# 10.net
KiCad netlist of a schematic drawn in Altium Designer
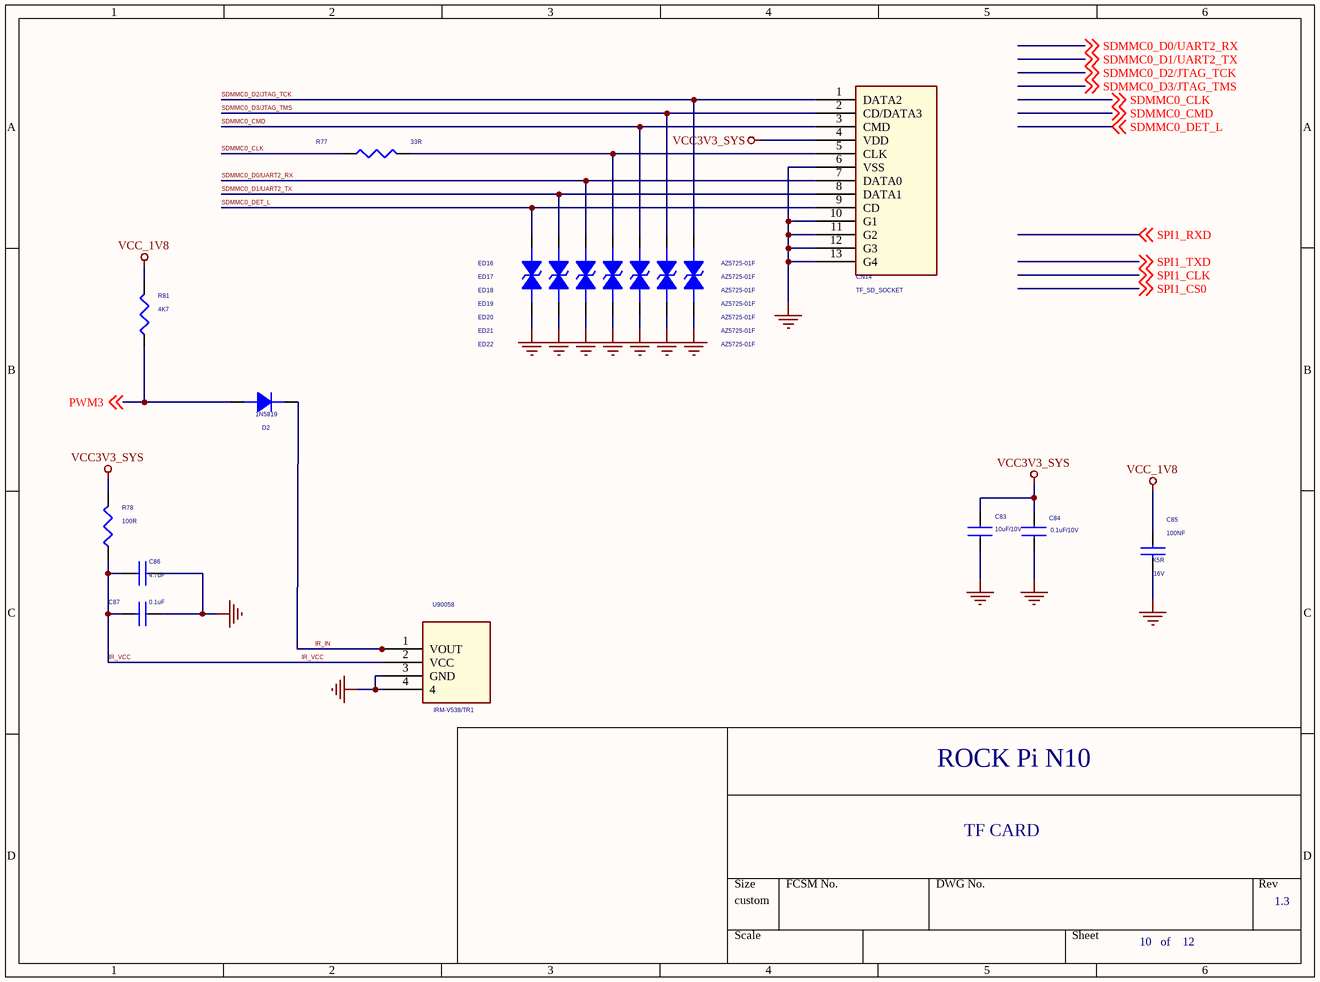
[diagram p0: 10.SchDoc]

(export (version "E")
  (design (tool "Eeschema 10.0.6"))
  (components
    (comp (ref "C83")
      (value "10uF/10V")
      (footprint "C0603")
      (description "CAP,MLCC,10uF,+/-10%,X5R,6.3V,SMD0805")
      (libsource (lib "*") (part "CAP NP_Dup4"))
    )
    (comp (ref "C84")
      (value "0.1uF/10V")
      (footprint "C0603")
      (description "CAP,MLCC,100nF,+/-10%,X7R,6.3V,SMD0402")
      (libsource (lib "*") (part "CAP NP_Dup4"))
    )
    (comp (ref "C85")
      (value "100NF")
      (footprint "C0402")
      (description "cap,100.00nF,+/-10%,16V,X5R,C0402")
      (fields
        (field (name "DIELECTRIC") "X5R")
        (field (name "VOLTAGE") "16V")
        (field (name "MANUFACTURER") "TDK")
        (field (name "TOLERANCE") "10%")
        (field (name "CREATED BY") "JJJ")
      )
      (libsource (lib "*") (part "CAP NP_2"))
    )
    (comp (ref "C86")
      (value "4.7uF")
      (footprint "C0402")
      (description "CAP,MLCC,10uF,+/-10%,X5R,6.3V,SMD0805")
      (libsource (lib "*") (part "CAP NP_Dup1"))
    )
    (comp (ref "C87") (value "0.1uF") (footprint "C0402") (libsource (lib "*") (part "CAP NP_4")))
    (comp (ref "CN14")
      (value "TF_SD_SOCKET")
      (footprint "TF-CKT01-009D")
      (libsource (lib "*") (part "SD_SOCKET_0"))
    )
    (comp (ref "D2")
      (value "1N5819")
      (footprint "SOD323")
      (description "RoHS 1.0A SURFACE MOUNT SCHOTTKY BARRIER RECTIFIER 1N5819")
      (libsource (lib "*") (part "DIODE_Dup1"))
    )
    (comp (ref "ED16")
      (value "AZ5725-01F")
      (footprint "E0402N")
      (description "ESD")
      (libsource (lib "*") (part "DIODE BI-DIR TRIG"))
    )
    (comp (ref "ED17")
      (value "AZ5725-01F")
      (footprint "E0402N")
      (description "ESD")
      (libsource (lib "*") (part "DIODE BI-DIR TRIG"))
    )
    (comp (ref "ED18")
      (value "AZ5725-01F")
      (footprint "E0402N")
      (description "ESD")
      (libsource (lib "*") (part "DIODE BI-DIR TRIG"))
    )
    (comp (ref "ED19")
      (value "AZ5725-01F")
      (footprint "E0402N")
      (description "ESD")
      (libsource (lib "*") (part "DIODE BI-DIR TRIG"))
    )
    (comp (ref "ED20")
      (value "AZ5725-01F")
      (footprint "E0402N")
      (description "ESD")
      (libsource (lib "*") (part "DIODE BI-DIR TRIG"))
    )
    (comp (ref "ED21")
      (value "AZ5725-01F")
      (footprint "E0402N")
      (description "ESD")
      (libsource (lib "*") (part "DIODE BI-DIR TRIG"))
    )
    (comp (ref "ED22")
      (value "AZ5725-01F")
      (footprint "E0402N")
      (description "ESD")
      (libsource (lib "*") (part "DIODE BI-DIR TRIG"))
    )
    (comp (ref "R77") (value "33R") (footprint "R0402") (libsource (lib "*") (part "RESISTOR_1")))
    (comp (ref "R78")
      (value "100R")
      (footprint "R0402")
      (description "RES,thick film,10Ohm,+/-5%,1/10W,SMD0603")
      (libsource (lib "*") (part "RESISTOR_Dup1"))
    )
    (comp (ref "R81")
      (value "4K7")
      (footprint "R0402")
      (description "RES,thick film,10KOhm,+/-5%,1/16W,SMD0402")
      (libsource (lib "*") (part "RESISTOR_Dup1"))
    )
    (comp (ref "U90058")
      (value "IRM-V538/TR1")
      (footprint "IRM-V538/TR1")
      (libsource (lib "*") (part "IRM-V538/TR1"))
    )
  )
  (nets
    (net (code "1") (name "/IR_IN") (class "Default")
      (node (ref "D2") (pin "2") (pinfunction "K_2") (pintype "passive"))
      (node (ref "U90058") (pin "1") (pinfunction "VOUT_1") (pintype "passive"))
    )
    (net (code "2") (name "/IR_VCC") (class "Default")
      (node (ref "C86") (pin "2") (pinfunction "2_2") (pintype "passive"))
      (node (ref "C87") (pin "2") (pinfunction "2_2") (pintype "passive"))
      (node (ref "R78") (pin "1") (pinfunction "1_1") (pintype "passive"))
      (node (ref "U90058") (pin "2") (pinfunction "VCC_2") (pintype "passive"))
    )
    (net (code "3") (name "GND") (class "Default")
      (node (ref "C83") (pin "1") (pinfunction "1_1") (pintype "passive"))
      (node (ref "C84") (pin "2") (pinfunction "2_2") (pintype "passive"))
      (node (ref "C85") (pin "2") (pinfunction "2_2") (pintype "passive"))
      (node (ref "C86") (pin "1") (pinfunction "1_1") (pintype "passive"))
      (node (ref "C87") (pin "1") (pinfunction "1_1") (pintype "passive"))
      (node (ref "CN14") (pin "10") (pinfunction "G1_10") (pintype "passive"))
      (node (ref "CN14") (pin "11") (pinfunction "G2_11") (pintype "passive"))
      (node (ref "CN14") (pin "12") (pinfunction "G3_12") (pintype "passive"))
      (node (ref "CN14") (pin "13") (pinfunction "G4_13") (pintype "passive"))
      (node (ref "CN14") (pin "6") (pinfunction "VSS_6") (pintype "passive"))
      (node (ref "ED16") (pin "2") (pinfunction "2_2") (pintype "passive"))
      (node (ref "ED17") (pin "2") (pinfunction "2_2") (pintype "passive"))
      (node (ref "ED18") (pin "2") (pinfunction "2_2") (pintype "passive"))
      (node (ref "ED19") (pin "2") (pinfunction "2_2") (pintype "passive"))
      (node (ref "ED20") (pin "2") (pinfunction "2_2") (pintype "passive"))
      (node (ref "ED21") (pin "2") (pinfunction "2_2") (pintype "passive"))
      (node (ref "ED22") (pin "2") (pinfunction "2_2") (pintype "passive"))
      (node (ref "U90058") (pin "3") (pinfunction "GND_3") (pintype "passive"))
      (node (ref "U90058") (pin "4") (pinfunction "4_4") (pintype "passive"))
    )
    (net (code "4") (name "Net-(CN14-CLK)") (class "Default")
      (node (ref "CN14") (pin "5") (pinfunction "CLK_5") (pintype "passive"))
      (node (ref "ED19") (pin "1") (pinfunction "1_1") (pintype "passive"))
      (node (ref "R77") (pin "2") (pinfunction "2_2") (pintype "passive"))
    )
    (net (code "5") (name "PWM3") (class "Default")
      (node (ref "D2") (pin "1") (pinfunction "A_1") (pintype "passive"))
      (node (ref "R81") (pin "1") (pinfunction "1_1") (pintype "passive"))
    )
    (net (code "6") (name "SDMMC0_CLK") (class "Default")
      (node (ref "R77") (pin "1") (pinfunction "1_1") (pintype "passive"))
    )
    (net (code "7") (name "SDMMC0_CMD") (class "Default")
      (node (ref "CN14") (pin "3") (pinfunction "CMD_3") (pintype "passive"))
      (node (ref "ED20") (pin "1") (pinfunction "1_1") (pintype "passive"))
    )
    (net (code "8") (name "SDMMC0_D0{slash}UART2_RX") (class "Default")
      (node (ref "CN14") (pin "7") (pinfunction "DATA0_7") (pintype "passive"))
      (node (ref "ED18") (pin "1") (pinfunction "1_1") (pintype "passive"))
    )
    (net (code "9") (name "SDMMC0_D1{slash}UART2_TX") (class "Default")
      (node (ref "CN14") (pin "8") (pinfunction "DATA1_8") (pintype "passive"))
      (node (ref "ED17") (pin "1") (pinfunction "1_1") (pintype "passive"))
    )
    (net (code "10") (name "SDMMC0_D2{slash}JTAG_TCK") (class "Default")
      (node (ref "CN14") (pin "1") (pinfunction "DATA2_1") (pintype "passive"))
      (node (ref "ED22") (pin "1") (pinfunction "1_1") (pintype "passive"))
    )
    (net (code "11") (name "SDMMC0_D3{slash}JTAG_TMS") (class "Default")
      (node (ref "CN14") (pin "2") (pinfunction "CD/DATA3_2") (pintype "passive"))
      (node (ref "ED21") (pin "1") (pinfunction "1_1") (pintype "passive"))
    )
    (net (code "12") (name "SDMMC0_DET_L") (class "Default")
      (node (ref "CN14") (pin "9") (pinfunction "CD_9") (pintype "passive"))
      (node (ref "ED16") (pin "1") (pinfunction "1_1") (pintype "passive"))
    )
    (net (code "17") (name "VCC3V3_SYS") (class "Default")
      (node (ref "C83") (pin "2") (pinfunction "2_2") (pintype "passive"))
      (node (ref "C84") (pin "1") (pinfunction "1_1") (pintype "passive"))
      (node (ref "CN14") (pin "4") (pinfunction "VDD_4") (pintype "passive"))
      (node (ref "R78") (pin "2") (pinfunction "2_2") (pintype "passive"))
    )
    (net (code "18") (name "VCC_1V8") (class "Default")
      (node (ref "C85") (pin "1") (pinfunction "1_1") (pintype "passive"))
      (node (ref "R81") (pin "2") (pinfunction "2_2") (pintype "passive"))
    )
  )
)
